# lm2596_current_limited_charger.net
KiCad netlist of a schematic drawn in EAGLE
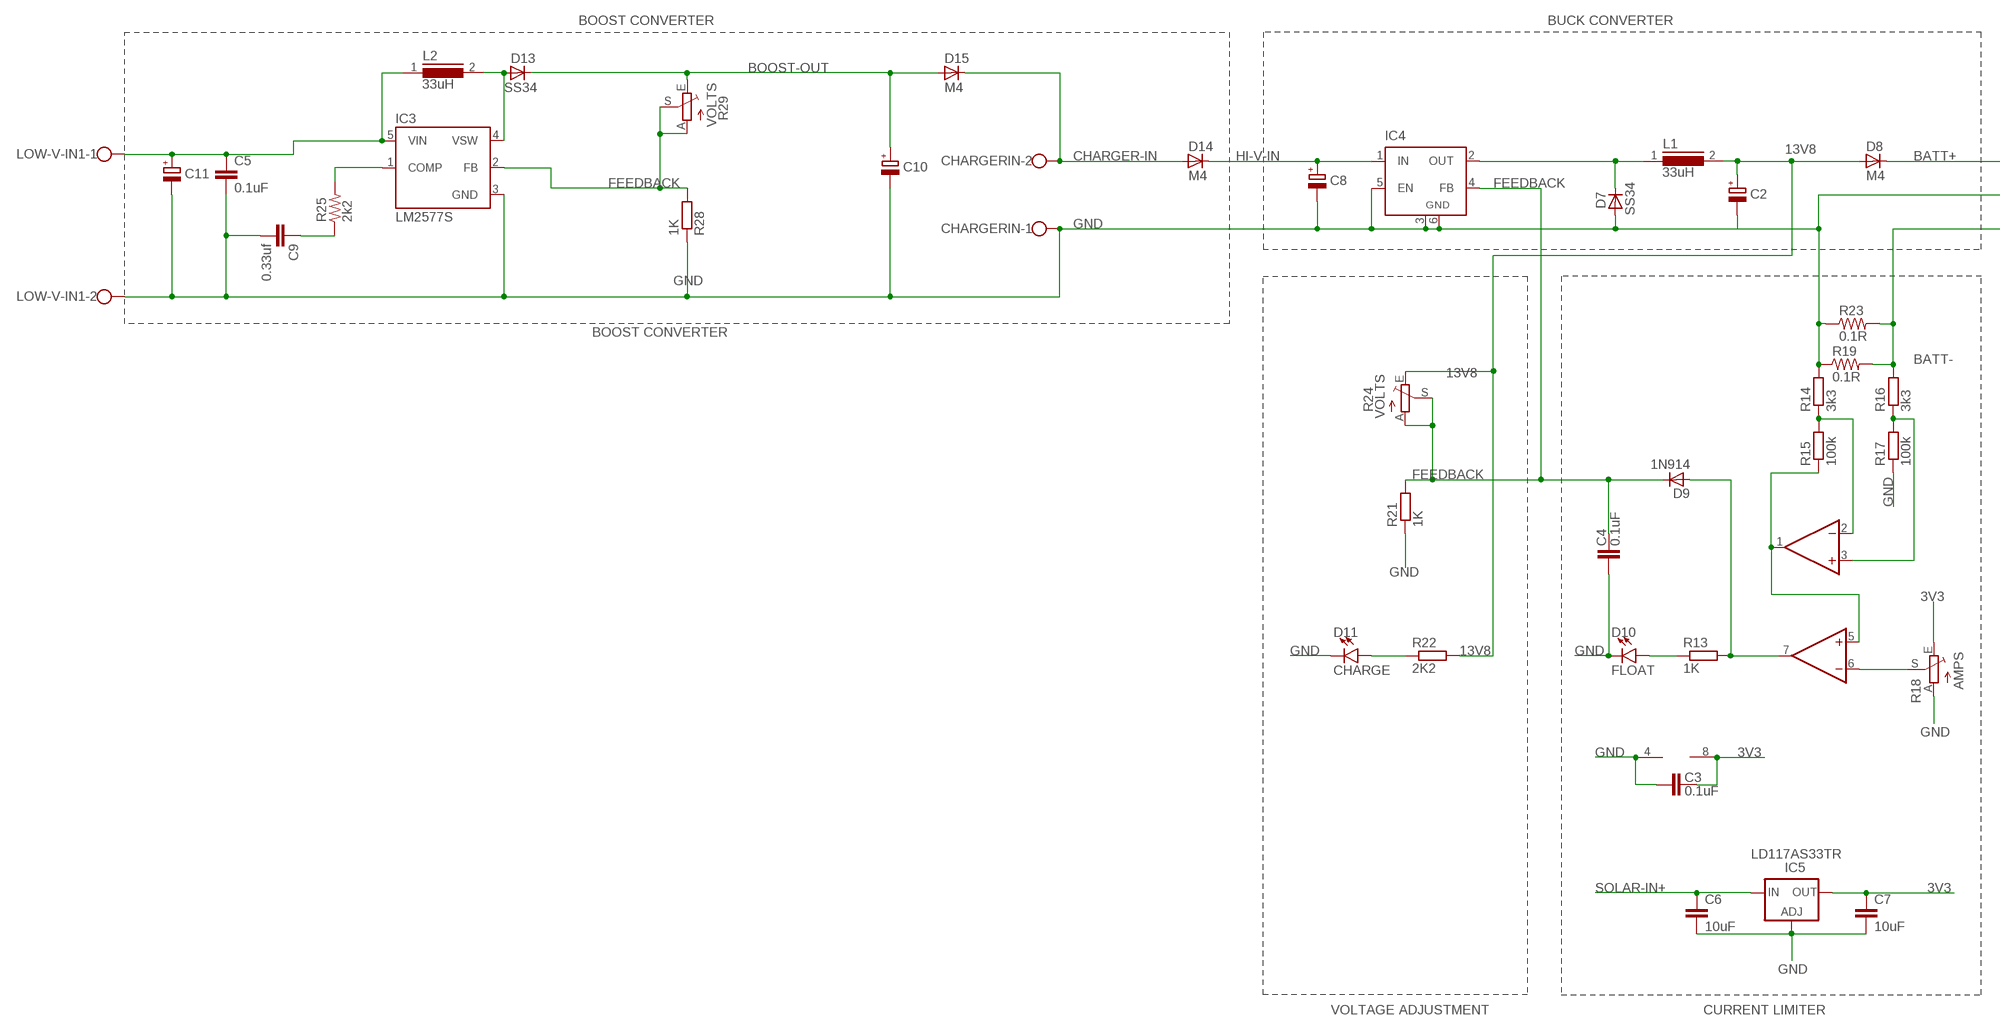
[diagram p0: schematic, sheet 1, part 1 of 2]
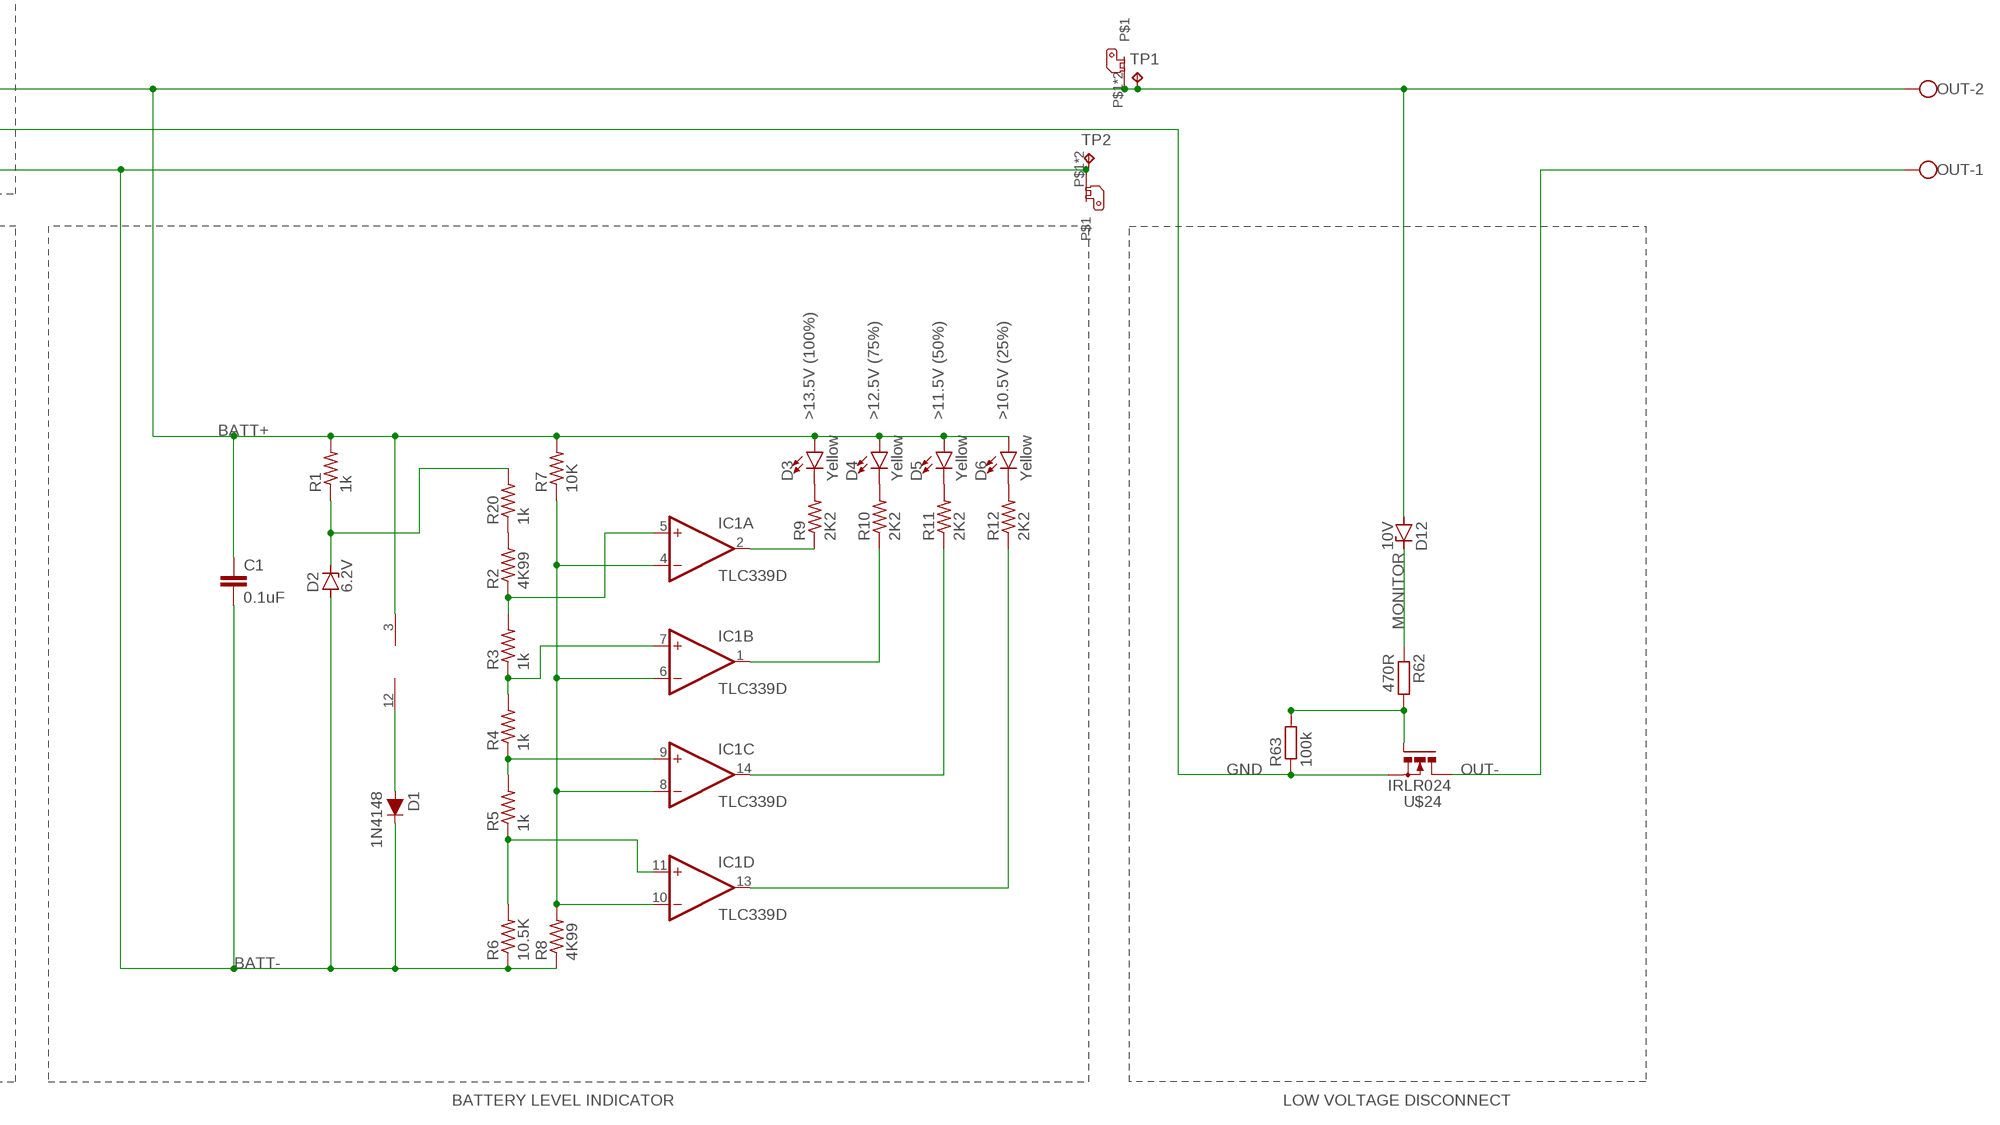
[diagram p1: schematic, sheet 1, part 2 of 2]

(export (version "E")
  (design (tool "Eeschema 10.0.6"))
  (components
    (comp (ref "C1")
      (value "0.1uF")
      (footprint "eagle-import:C1206K")
      (libsource (lib "eagle-import") (part "C-EUC1206K"))
    )
    (comp (ref "C2")
      (value "CPOL-EUE3.5-8")
      (footprint "eagle-import:E3,5-8")
      (libsource (lib "eagle-import") (part "CPOL-EUE3.5-8"))
    )
    (comp (ref "C3")
      (value "0.1uF")
      (footprint "eagle-import:C1206K")
      (libsource (lib "eagle-import") (part "C-EUC1206K"))
    )
    (comp (ref "C4")
      (value "0.1uF")
      (footprint "eagle-import:C1206K")
      (libsource (lib "eagle-import") (part "C-EUC1206K"))
    )
    (comp (ref "C5")
      (value "0.1uF")
      (footprint "eagle-import:C1206K")
      (libsource (lib "eagle-import") (part "C-EUC1206K"))
    )
    (comp (ref "C6")
      (value "10uF")
      (footprint "eagle-import:C1206K")
      (libsource (lib "eagle-import") (part "C-EUC1206K"))
    )
    (comp (ref "C7")
      (value "10uF")
      (footprint "eagle-import:C1206K")
      (libsource (lib "eagle-import") (part "C-EUC1206K"))
    )
    (comp (ref "C8")
      (value "CPOL-EUE3.5-8")
      (footprint "eagle-import:E3,5-8")
      (libsource (lib "eagle-import") (part "CPOL-EUE3.5-8"))
    )
    (comp (ref "C9")
      (value "0.33uf")
      (footprint "eagle-import:C1206K")
      (libsource (lib "eagle-import") (part "C-EUC1206K"))
    )
    (comp (ref "C10")
      (value "CPOL-EUE3.5-8")
      (footprint "eagle-import:E3,5-8")
      (libsource (lib "eagle-import") (part "CPOL-EUE3.5-8"))
    )
    (comp (ref "C11")
      (value "CPOL-EUE3.5-8")
      (footprint "eagle-import:E3,5-8")
      (libsource (lib "eagle-import") (part "CPOL-EUE3.5-8"))
    )
    (comp (ref "CHARGERIN")
      (value "W237-102")
      (footprint "eagle-import:W237-102")
      (fields (field (name "MPN") "237-102"))
      (libsource (lib "eagle-import") (part "W237-102"))
    )
    (comp (ref "D1")
      (value "1N4148")
      (footprint "eagle-import:SOD-323")
      (libsource (lib "eagle-import") (part "DIODE-BAS16J"))
    )
    (comp (ref "D2")
      (value "6.2V")
      (footprint "eagle-import:SMB")
      (libsource (lib "eagle-import") (part "ZENER-DIODESMB"))
    )
    (comp (ref "D3")
      (value "Yellow")
      (footprint "eagle-import:LED-1206")
      (libsource (lib "eagle-import") (part "LED-YELLOWLILYPAD"))
    )
    (comp (ref "D4")
      (value "Yellow")
      (footprint "eagle-import:LED-1206")
      (libsource (lib "eagle-import") (part "LED-YELLOWLILYPAD"))
    )
    (comp (ref "D5")
      (value "Yellow")
      (footprint "eagle-import:LED-1206")
      (libsource (lib "eagle-import") (part "LED-YELLOWLILYPAD"))
    )
    (comp (ref "D6")
      (value "Yellow")
      (footprint "eagle-import:LED-1206")
      (libsource (lib "eagle-import") (part "LED-YELLOWLILYPAD"))
    )
    (comp (ref "D7")
      (value "SS34")
      (footprint "eagle-import:SOD87")
      (libsource (lib "eagle-import") (part "D-SOD-87"))
    )
    (comp (ref "D8")
      (value "M4")
      (footprint "eagle-import:SOD87")
      (libsource (lib "eagle-import") (part "D-SOD-87"))
    )
    (comp (ref "D9")
      (value "1N914")
      (footprint "eagle-import:SOD87")
      (libsource (lib "eagle-import") (part "D-SOD-87"))
    )
    (comp (ref "D10")
      (value "FLOAT")
      (footprint "eagle-import:LED-1206")
      (libsource (lib "eagle-import") (part "LED-YELLOWLILYPAD"))
    )
    (comp (ref "D11")
      (value "CHARGE")
      (footprint "eagle-import:LED-1206")
      (libsource (lib "eagle-import") (part "LED-YELLOWLILYPAD"))
    )
    (comp (ref "D12")
      (value "10V")
      (footprint "eagle-import:SMB")
      (libsource (lib "eagle-import") (part "ZENER-DIODESMB"))
    )
    (comp (ref "D13")
      (value "SS34")
      (footprint "eagle-import:SOD87")
      (libsource (lib "eagle-import") (part "D-SOD-87"))
    )
    (comp (ref "D14")
      (value "M4")
      (footprint "eagle-import:SOD87")
      (libsource (lib "eagle-import") (part "D-SOD-87"))
    )
    (comp (ref "D15")
      (value "M4")
      (footprint "eagle-import:SOD87")
      (libsource (lib "eagle-import") (part "D-SOD-87"))
    )
    (comp (ref "IC1")
      (value "TLC339D")
      (footprint "eagle-import:SO14")
      (libsource (lib "eagle-import") (part "TLC339D"))
    )
    (comp (ref "IC2")
      (value "MCP602SN")
      (footprint "eagle-import:SO08")
      (libsource (lib "eagle-import") (part "MCP602SN"))
    )
    (comp (ref "IC3")
      (value "LM2577S")
      (footprint "eagle-import:TO263-5")
      (libsource (lib "eagle-import") (part "LM2577S"))
    )
    (comp (ref "IC4")
      (value "LM2596S")
      (footprint "eagle-import:TO263-5")
      (libsource (lib "eagle-import") (part "LM2596S"))
    )
    (comp (ref "IC5")
      (value "LD117AS33TR")
      (footprint "eagle-import:SOT223")
      (libsource (lib "eagle-import") (part "LD117A?S33TR"))
    )
    (comp (ref "L1")
      (value "33uH")
      (footprint "eagle-import:DR127")
      (libsource (lib "eagle-import") (part "DR127"))
    )
    (comp (ref "L2")
      (value "33uH")
      (footprint "eagle-import:DR127")
      (libsource (lib "eagle-import") (part "DR127"))
    )
    (comp (ref "LOW-V-IN1")
      (value "W237-102")
      (footprint "eagle-import:W237-102")
      (fields (field (name "MPN") "237-102"))
      (libsource (lib "eagle-import") (part "W237-102"))
    )
    (comp (ref "OUT")
      (value "W237-102")
      (footprint "eagle-import:W237-102")
      (fields (field (name "MPN") "237-102"))
      (libsource (lib "eagle-import") (part "W237-102"))
    )
    (comp (ref "R1")
      (value "1k")
      (footprint "eagle-import:R1206")
      (libsource (lib "eagle-import") (part "R-US_R1206"))
    )
    (comp (ref "R2")
      (value "4K99")
      (footprint "eagle-import:R1206")
      (libsource (lib "eagle-import") (part "R-US_R1206"))
    )
    (comp (ref "R3")
      (value "1k")
      (footprint "eagle-import:R1206")
      (libsource (lib "eagle-import") (part "R-US_R1206"))
    )
    (comp (ref "R4")
      (value "1k")
      (footprint "eagle-import:R1206")
      (libsource (lib "eagle-import") (part "R-US_R1206"))
    )
    (comp (ref "R5")
      (value "1k")
      (footprint "eagle-import:R1206")
      (libsource (lib "eagle-import") (part "R-US_R1206"))
    )
    (comp (ref "R6")
      (value "10.5K")
      (footprint "eagle-import:R1206")
      (libsource (lib "eagle-import") (part "R-US_R1206"))
    )
    (comp (ref "R7")
      (value "10K")
      (footprint "eagle-import:R1206")
      (libsource (lib "eagle-import") (part "R-US_R1206"))
    )
    (comp (ref "R8")
      (value "4K99")
      (footprint "eagle-import:R1206")
      (libsource (lib "eagle-import") (part "R-US_R1206"))
    )
    (comp (ref "R9")
      (value "2K2")
      (footprint "eagle-import:R1206")
      (libsource (lib "eagle-import") (part "R-US_R1206"))
    )
    (comp (ref "R10")
      (value "2K2")
      (footprint "eagle-import:R1206")
      (libsource (lib "eagle-import") (part "R-US_R1206"))
    )
    (comp (ref "R11")
      (value "2K2")
      (footprint "eagle-import:R1206")
      (libsource (lib "eagle-import") (part "R-US_R1206"))
    )
    (comp (ref "R12")
      (value "2K2")
      (footprint "eagle-import:R1206")
      (libsource (lib "eagle-import") (part "R-US_R1206"))
    )
    (comp (ref "R13")
      (value "1K")
      (footprint "eagle-import:R1206")
      (libsource (lib "eagle-import") (part "R-EU_R1206"))
    )
    (comp (ref "R14")
      (value "3k3")
      (footprint "eagle-import:R1206")
      (libsource (lib "eagle-import") (part "R-EU_R1206"))
    )
    (comp (ref "R15")
      (value "100k")
      (footprint "eagle-import:R1206")
      (libsource (lib "eagle-import") (part "R-EU_R1206"))
    )
    (comp (ref "R16")
      (value "3k3")
      (footprint "eagle-import:R1206")
      (libsource (lib "eagle-import") (part "R-EU_R1206"))
    )
    (comp (ref "R17")
      (value "100k")
      (footprint "eagle-import:R1206")
      (libsource (lib "eagle-import") (part "R-EU_R1206"))
    )
    (comp (ref "R18")
      (value "AMPS")
      (footprint "eagle-import:B64Y")
      (libsource (lib "eagle-import") (part "TRIM_EU-B64Y"))
    )
    (comp (ref "R19")
      (value "0.1R")
      (footprint "eagle-import:R2512")
      (libsource (lib "eagle-import") (part "R-US_R2512"))
    )
    (comp (ref "R20")
      (value "1k")
      (footprint "eagle-import:R1206")
      (libsource (lib "eagle-import") (part "R-US_R1206"))
    )
    (comp (ref "R21")
      (value "1K")
      (footprint "eagle-import:R1206")
      (libsource (lib "eagle-import") (part "R-EU_R1206"))
    )
    (comp (ref "R22")
      (value "2K2")
      (footprint "eagle-import:R1206")
      (libsource (lib "eagle-import") (part "R-EU_R1206"))
    )
    (comp (ref "R23")
      (value "0.1R")
      (footprint "eagle-import:R2512")
      (libsource (lib "eagle-import") (part "R-US_R2512"))
    )
    (comp (ref "R24")
      (value "VOLTS")
      (footprint "eagle-import:B64Y")
      (libsource (lib "eagle-import") (part "TRIM_EU-B64Y"))
    )
    (comp (ref "R25")
      (value "2k2")
      (footprint "eagle-import:R2512")
      (libsource (lib "eagle-import") (part "R-US_R2512"))
    )
    (comp (ref "R28")
      (value "1K")
      (footprint "eagle-import:R1206")
      (libsource (lib "eagle-import") (part "R-EU_R1206"))
    )
    (comp (ref "R29")
      (value "VOLTS")
      (footprint "eagle-import:B64Y")
      (libsource (lib "eagle-import") (part "TRIM_EU-B64Y"))
    )
    (comp (ref "R62")
      (value "470R")
      (footprint "eagle-import:R0603")
      (libsource (lib "eagle-import") (part "resistor_R-EU_R0603"))
    )
    (comp (ref "R63")
      (value "100k")
      (footprint "eagle-import:R0603")
      (libsource (lib "eagle-import") (part "resistor_R-EU_R0603"))
    )
    (comp (ref "TP1")
      (value "TPPAD1-20Y")
      (footprint "eagle-import:P1-20Y")
      (libsource (lib "eagle-import") (part "TPPAD1-20Y"))
    )
    (comp (ref "TP2")
      (value "TPPAD1-20Y")
      (footprint "eagle-import:P1-20Y")
      (libsource (lib "eagle-import") (part "TPPAD1-20Y"))
    )
    (comp (ref "U$2")
      (value "PCB-6.35MM-RA-SPADE")
      (footprint "eagle-import:PCB-6.35MM-RA-SPADE")
      (libsource (lib "eagle-import") (part "PCB-6.35MM-RA-SPADE"))
    )
    (comp (ref "U$3")
      (value "PCB-6.35MM-RA-SPADE")
      (footprint "eagle-import:PCB-6.35MM-RA-SPADE")
      (libsource (lib "eagle-import") (part "PCB-6.35MM-RA-SPADE"))
    )
    (comp (ref "U$24")
      (value "IRLR024")
      (footprint "eagle-import:D-PAK_TO252AA")
      (libsource (lib "eagle-import") (part "N-POWER-MOSFETDPAK-MOSFET"))
    )
  )
  (nets
    (net (code "1") (name "/3V3") (class "Default")
      (node (ref "C3") (pin "2") (pinfunction "2_2") (pintype "passive"))
      (node (ref "C7") (pin "1") (pinfunction "1_1") (pintype "passive"))
      (node (ref "IC2") (pin "8") (pinfunction "V+_8") (pintype "power_in"))
      (node (ref "IC5") (pin "4") (pinfunction "OUT_4") (pintype "passive"))
      (node (ref "R18") (pin "E") (pinfunction "E_E") (pintype "passive"))
    )
    (net (code "2") (name "/13V8") (class "Default")
      (node (ref "C2") (pin "+") (pinfunction "+_+") (pintype "passive"))
      (node (ref "D8") (pin "2") (pinfunction "A_2") (pintype "passive"))
      (node (ref "L1") (pin "2") (pinfunction "2_2") (pintype "passive"))
      (node (ref "R22") (pin "2") (pinfunction "2_2") (pintype "passive"))
      (node (ref "R24") (pin "E") (pinfunction "E_E") (pintype "passive"))
    )
    (net (code "3") (name "/BATT+") (class "Default")
      (node (ref "C1") (pin "1") (pinfunction "1_1") (pintype "passive"))
      (node (ref "D12") (pin "A") (pinfunction "A_A") (pintype "passive"))
      (node (ref "D3") (pin "A") (pinfunction "A_A") (pintype "passive"))
      (node (ref "D4") (pin "A") (pinfunction "A_A") (pintype "passive"))
      (node (ref "D5") (pin "A") (pinfunction "A_A") (pintype "passive"))
      (node (ref "D6") (pin "A") (pinfunction "A_A") (pintype "passive"))
      (node (ref "D8") (pin "1") (pinfunction "C_1") (pintype "passive"))
      (node (ref "IC1") (pin "3") (pinfunction "V+_3") (pintype "power_in"))
      (node (ref "OUT") (pin "2") (pinfunction "KL_2") (pintype "passive"))
      (node (ref "R1") (pin "2") (pinfunction "2_2") (pintype "passive"))
      (node (ref "R7") (pin "2") (pinfunction "2_2") (pintype "passive"))
      (node (ref "TP1") (pin "TP") (pinfunction "TP_TP") (pintype "input"))
      (node (ref "U$2") (pin "P$1") (pinfunction "P$1_P$1") (pintype "bidirectional"))
      (node (ref "U$2") (pin "P$2") (pinfunction "P$1_P$2") (pintype "bidirectional"))
    )
    (net (code "4") (name "/BATT-") (class "Default")
      (node (ref "C1") (pin "2") (pinfunction "2_2") (pintype "passive"))
      (node (ref "D1") (pin "C") (pinfunction "C_C") (pintype "passive"))
      (node (ref "D2") (pin "A") (pinfunction "A_A") (pintype "passive"))
      (node (ref "R16") (pin "2") (pinfunction "2_2") (pintype "passive"))
      (node (ref "R19") (pin "2") (pinfunction "2_2") (pintype "passive"))
      (node (ref "R23") (pin "2") (pinfunction "2_2") (pintype "passive"))
      (node (ref "R6") (pin "1") (pinfunction "1_1") (pintype "passive"))
      (node (ref "R8") (pin "1") (pinfunction "1_1") (pintype "passive"))
      (node (ref "TP2") (pin "TP") (pinfunction "TP_TP") (pintype "input"))
      (node (ref "U$3") (pin "P$1") (pinfunction "P$1_P$1") (pintype "bidirectional"))
      (node (ref "U$3") (pin "P$2") (pinfunction "P$1_P$2") (pintype "bidirectional"))
    )
    (net (code "5") (name "/BOOST-OUT") (class "Default")
      (node (ref "C10") (pin "+") (pinfunction "+_+") (pintype "passive"))
      (node (ref "D13") (pin "1") (pinfunction "C_1") (pintype "passive"))
      (node (ref "D15") (pin "2") (pinfunction "A_2") (pintype "passive"))
      (node (ref "R29") (pin "E") (pinfunction "E_E") (pintype "passive"))
    )
    (net (code "6") (name "/CHARGER-IN") (class "Default")
      (node (ref "CHARGERIN") (pin "2") (pinfunction "KL_2") (pintype "passive"))
      (node (ref "D14") (pin "2") (pinfunction "A_2") (pintype "passive"))
      (node (ref "D15") (pin "1") (pinfunction "C_1") (pintype "passive"))
    )
    (net (code "7") (name "/FEEDBACK") (class "Default")
      (node (ref "C4") (pin "2") (pinfunction "2_2") (pintype "passive"))
      (node (ref "D9") (pin "1") (pinfunction "C_1") (pintype "passive"))
      (node (ref "IC3") (pin "2") (pinfunction "FB_2") (pintype "input"))
      (node (ref "IC4") (pin "4") (pinfunction "FB_4") (pintype "input"))
      (node (ref "R21") (pin "2") (pinfunction "2_2") (pintype "passive"))
      (node (ref "R24") (pin "A") (pinfunction "A_A") (pintype "passive"))
      (node (ref "R24") (pin "S") (pinfunction "S_S") (pintype "passive"))
      (node (ref "R28") (pin "2") (pinfunction "2_2") (pintype "passive"))
      (node (ref "R29") (pin "A") (pinfunction "A_A") (pintype "passive"))
      (node (ref "R29") (pin "S") (pinfunction "S_S") (pintype "passive"))
    )
    (net (code "8") (name "/GND") (class "Default")
      (node (ref "C10") (pin "-") (pinfunction "-_-") (pintype "passive"))
      (node (ref "C11") (pin "-") (pinfunction "-_-") (pintype "passive"))
      (node (ref "C2") (pin "-") (pinfunction "-_-") (pintype "passive"))
      (node (ref "C3") (pin "1") (pinfunction "1_1") (pintype "passive"))
      (node (ref "C4") (pin "1") (pinfunction "1_1") (pintype "passive"))
      (node (ref "C5") (pin "2") (pinfunction "2_2") (pintype "passive"))
      (node (ref "C6") (pin "2") (pinfunction "2_2") (pintype "passive"))
      (node (ref "C7") (pin "2") (pinfunction "2_2") (pintype "passive"))
      (node (ref "C8") (pin "-") (pinfunction "-_-") (pintype "passive"))
      (node (ref "C9") (pin "2") (pinfunction "2_2") (pintype "passive"))
      (node (ref "CHARGERIN") (pin "1") (pinfunction "KL_1") (pintype "passive"))
      (node (ref "D10") (pin "C") (pinfunction "C_C") (pintype "passive"))
      (node (ref "D11") (pin "C") (pinfunction "C_C") (pintype "passive"))
      (node (ref "D7") (pin "2") (pinfunction "A_2") (pintype "passive"))
      (node (ref "IC2") (pin "4") (pinfunction "V-_4") (pintype "power_in"))
      (node (ref "IC3") (pin "3") (pinfunction "GND_3") (pintype "power_in"))
      (node (ref "IC4") (pin "3") (pinfunction "GND_3") (pintype "power_in"))
      (node (ref "IC4") (pin "5") (pinfunction "EN_5") (pintype "input"))
      (node (ref "IC4") (pin "6") (pinfunction "GND_6") (pintype "power_in"))
      (node (ref "IC5") (pin "1") (pinfunction "ADJ_1") (pintype "input"))
      (node (ref "LOW-V-IN1") (pin "2") (pinfunction "KL_2") (pintype "passive"))
      (node (ref "R14") (pin "2") (pinfunction "2_2") (pintype "passive"))
      (node (ref "R17") (pin "1") (pinfunction "1_1") (pintype "passive"))
      (node (ref "R18") (pin "A") (pinfunction "A_A") (pintype "passive"))
      (node (ref "R19") (pin "1") (pinfunction "1_1") (pintype "passive"))
      (node (ref "R21") (pin "1") (pinfunction "1_1") (pintype "passive"))
      (node (ref "R23") (pin "1") (pinfunction "1_1") (pintype "passive"))
      (node (ref "R28") (pin "1") (pinfunction "1_1") (pintype "passive"))
      (node (ref "R63") (pin "1") (pinfunction "1_1") (pintype "passive"))
      (node (ref "U$24") (pin "3") (pinfunction "S_3") (pintype "passive"))
    )
    (net (code "9") (name "/HI-V-IN") (class "Default")
      (node (ref "C8") (pin "+") (pinfunction "+_+") (pintype "passive"))
      (node (ref "D14") (pin "1") (pinfunction "C_1") (pintype "passive"))
      (node (ref "IC4") (pin "1") (pinfunction "IN_1") (pintype "input"))
    )
    (net (code "10") (name "/MONITOR") (class "Default")
      (node (ref "D12") (pin "C") (pinfunction "C_C") (pintype "passive"))
      (node (ref "R62") (pin "1") (pinfunction "1_1") (pintype "passive"))
    )
    (net (code "11") (name "/OUT-") (class "Default")
      (node (ref "OUT") (pin "1") (pinfunction "KL_1") (pintype "passive"))
      (node (ref "U$24") (pin "4") (pinfunction "D_4") (pintype "passive"))
    )
    (net (code "12") (name "/SOLAR-IN+") (class "Default")
      (node (ref "C6") (pin "1") (pinfunction "1_1") (pintype "passive"))
      (node (ref "IC5") (pin "3") (pinfunction "IN_3") (pintype "input"))
    )
    (net (code "13") (name "Net-(C9-Pad1)") (class "Default")
      (node (ref "C9") (pin "1") (pinfunction "1_1") (pintype "passive"))
      (node (ref "R25") (pin "1") (pinfunction "1_1") (pintype "passive"))
    )
    (net (code "14") (name "Net-(D2-PadC)") (class "Default")
      (node (ref "D2") (pin "C") (pinfunction "C_C") (pintype "passive"))
      (node (ref "R1") (pin "1") (pinfunction "1_1") (pintype "passive"))
      (node (ref "R20") (pin "2") (pinfunction "2_2") (pintype "passive"))
    )
    (net (code "15") (name "Net-(D3-PadC)") (class "Default")
      (node (ref "D3") (pin "C") (pinfunction "C_C") (pintype "passive"))
      (node (ref "R9") (pin "2") (pinfunction "2_2") (pintype "passive"))
    )
    (net (code "16") (name "Net-(D4-PadC)") (class "Default")
      (node (ref "D4") (pin "C") (pinfunction "C_C") (pintype "passive"))
      (node (ref "R10") (pin "2") (pinfunction "2_2") (pintype "passive"))
    )
    (net (code "17") (name "Net-(D5-PadC)") (class "Default")
      (node (ref "D5") (pin "C") (pinfunction "C_C") (pintype "passive"))
      (node (ref "R11") (pin "2") (pinfunction "2_2") (pintype "passive"))
    )
    (net (code "18") (name "Net-(D6-PadC)") (class "Default")
      (node (ref "D6") (pin "C") (pinfunction "C_C") (pintype "passive"))
      (node (ref "R12") (pin "2") (pinfunction "2_2") (pintype "passive"))
    )
    (net (code "19") (name "Net-(D7-C)") (class "Default")
      (node (ref "D7") (pin "1") (pinfunction "C_1") (pintype "passive"))
      (node (ref "IC4") (pin "2") (pinfunction "OUT_2") (pintype "output"))
      (node (ref "L1") (pin "1") (pinfunction "1_1") (pintype "passive"))
    )
    (net (code "20") (name "Net-(D9-A)") (class "Default")
      (node (ref "D9") (pin "2") (pinfunction "A_2") (pintype "passive"))
      (node (ref "IC2") (pin "7") (pinfunction "OUT_7") (pintype "output"))
      (node (ref "R13") (pin "2") (pinfunction "2_2") (pintype "passive"))
    )
    (net (code "21") (name "Net-(D10-PadA)") (class "Default")
      (node (ref "D10") (pin "A") (pinfunction "A_A") (pintype "passive"))
      (node (ref "R13") (pin "1") (pinfunction "1_1") (pintype "passive"))
    )
    (net (code "22") (name "Net-(D11-PadA)") (class "Default")
      (node (ref "D11") (pin "A") (pinfunction "A_A") (pintype "passive"))
      (node (ref "R22") (pin "1") (pinfunction "1_1") (pintype "passive"))
    )
    (net (code "23") (name "Net-(D13-A)") (class "Default")
      (node (ref "D13") (pin "2") (pinfunction "A_2") (pintype "passive"))
      (node (ref "IC3") (pin "4") (pinfunction "VSW_4") (pintype "bidirectional"))
      (node (ref "L2") (pin "2") (pinfunction "2_2") (pintype "passive"))
    )
    (net (code "24") (name "Net-(IC1A-+IN)") (class "Default")
      (node (ref "IC1") (pin "5") (pinfunction "+IN_5") (pintype "input"))
      (node (ref "R2") (pin "1") (pinfunction "1_1") (pintype "passive"))
      (node (ref "R3") (pin "2") (pinfunction "2_2") (pintype "passive"))
    )
    (net (code "25") (name "Net-(IC1A--IN)") (class "Default")
      (node (ref "IC1") (pin "10") (pinfunction "-IN_10") (pintype "input"))
      (node (ref "IC1") (pin "4") (pinfunction "-IN_4") (pintype "input"))
      (node (ref "IC1") (pin "6") (pinfunction "-IN_6") (pintype "input"))
      (node (ref "IC1") (pin "8") (pinfunction "-IN_8") (pintype "input"))
      (node (ref "R7") (pin "1") (pinfunction "1_1") (pintype "passive"))
      (node (ref "R8") (pin "2") (pinfunction "2_2") (pintype "passive"))
    )
    (net (code "26") (name "Net-(IC1A-OUT)") (class "Default")
      (node (ref "IC1") (pin "2") (pinfunction "OUT_2") (pintype "output"))
      (node (ref "R9") (pin "1") (pinfunction "1_1") (pintype "passive"))
    )
    (net (code "27") (name "Net-(IC1B-+IN)") (class "Default")
      (node (ref "IC1") (pin "7") (pinfunction "+IN_7") (pintype "input"))
      (node (ref "R3") (pin "1") (pinfunction "1_1") (pintype "passive"))
      (node (ref "R4") (pin "2") (pinfunction "2_2") (pintype "passive"))
    )
    (net (code "28") (name "Net-(IC1B-OUT)") (class "Default")
      (node (ref "IC1") (pin "1") (pinfunction "OUT_1") (pintype "output"))
      (node (ref "R10") (pin "1") (pinfunction "1_1") (pintype "passive"))
    )
    (net (code "29") (name "Net-(IC1C-+IN)") (class "Default")
      (node (ref "IC1") (pin "9") (pinfunction "+IN_9") (pintype "input"))
      (node (ref "R4") (pin "1") (pinfunction "1_1") (pintype "passive"))
      (node (ref "R5") (pin "2") (pinfunction "2_2") (pintype "passive"))
    )
    (net (code "30") (name "Net-(IC1C-OUT)") (class "Default")
      (node (ref "IC1") (pin "14") (pinfunction "OUT_14") (pintype "output"))
      (node (ref "R11") (pin "1") (pinfunction "1_1") (pintype "passive"))
    )
    (net (code "31") (name "Net-(IC1D-+IN)") (class "Default")
      (node (ref "IC1") (pin "11") (pinfunction "+IN_11") (pintype "input"))
      (node (ref "R5") (pin "1") (pinfunction "1_1") (pintype "passive"))
      (node (ref "R6") (pin "2") (pinfunction "2_2") (pintype "passive"))
    )
    (net (code "32") (name "Net-(IC1D-OUT)") (class "Default")
      (node (ref "IC1") (pin "13") (pinfunction "OUT_13") (pintype "output"))
      (node (ref "R12") (pin "1") (pinfunction "1_1") (pintype "passive"))
    )
    (net (code "33") (name "Net-(IC1E-V-)") (class "Default")
      (node (ref "D1") (pin "A") (pinfunction "A_A") (pintype "passive"))
      (node (ref "IC1") (pin "12") (pinfunction "V-_12") (pintype "power_in"))
    )
    (net (code "34") (name "Net-(IC2A-+IN)") (class "Default")
      (node (ref "IC2") (pin "3") (pinfunction "+IN_3") (pintype "input"))
      (node (ref "R16") (pin "1") (pinfunction "1_1") (pintype "passive"))
      (node (ref "R17") (pin "2") (pinfunction "2_2") (pintype "passive"))
    )
    (net (code "35") (name "Net-(IC2A--IN)") (class "Default")
      (node (ref "IC2") (pin "2") (pinfunction "-IN_2") (pintype "input"))
      (node (ref "R14") (pin "1") (pinfunction "1_1") (pintype "passive"))
      (node (ref "R15") (pin "2") (pinfunction "2_2") (pintype "passive"))
    )
    (net (code "36") (name "Net-(IC2A-OUT)") (class "Default")
      (node (ref "IC2") (pin "1") (pinfunction "OUT_1") (pintype "output"))
      (node (ref "IC2") (pin "5") (pinfunction "+IN_5") (pintype "input"))
      (node (ref "R15") (pin "1") (pinfunction "1_1") (pintype "passive"))
    )
    (net (code "37") (name "Net-(IC2B--IN)") (class "Default")
      (node (ref "IC2") (pin "6") (pinfunction "-IN_6") (pintype "input"))
      (node (ref "R18") (pin "S") (pinfunction "S_S") (pintype "passive"))
    )
    (net (code "38") (name "Net-(IC3-COMP)") (class "Default")
      (node (ref "IC3") (pin "1") (pinfunction "COMP_1") (pintype "passive"))
      (node (ref "R25") (pin "2") (pinfunction "2_2") (pintype "passive"))
    )
    (net (code "39") (name "Net-(IC3-VIN)") (class "Default")
      (node (ref "C11") (pin "+") (pinfunction "+_+") (pintype "passive"))
      (node (ref "C5") (pin "1") (pinfunction "1_1") (pintype "passive"))
      (node (ref "IC3") (pin "5") (pinfunction "VIN_5") (pintype "power_in"))
      (node (ref "L2") (pin "1") (pinfunction "1_1") (pintype "passive"))
      (node (ref "LOW-V-IN1") (pin "1") (pinfunction "KL_1") (pintype "passive"))
    )
    (net (code "40") (name "Net-(R2-Pad2)") (class "Default")
      (node (ref "R2") (pin "2") (pinfunction "2_2") (pintype "passive"))
      (node (ref "R20") (pin "1") (pinfunction "1_1") (pintype "passive"))
    )
    (net (code "41") (name "Net-(U$24-G)") (class "Default")
      (node (ref "R62") (pin "2") (pinfunction "2_2") (pintype "passive"))
      (node (ref "R63") (pin "2") (pinfunction "2_2") (pintype "passive"))
      (node (ref "U$24") (pin "1") (pinfunction "G_1") (pintype "passive"))
    )
  )
)
